# SCS_5V_RevA.net
KiCad netlist of a schematic drawn in Altium Designer
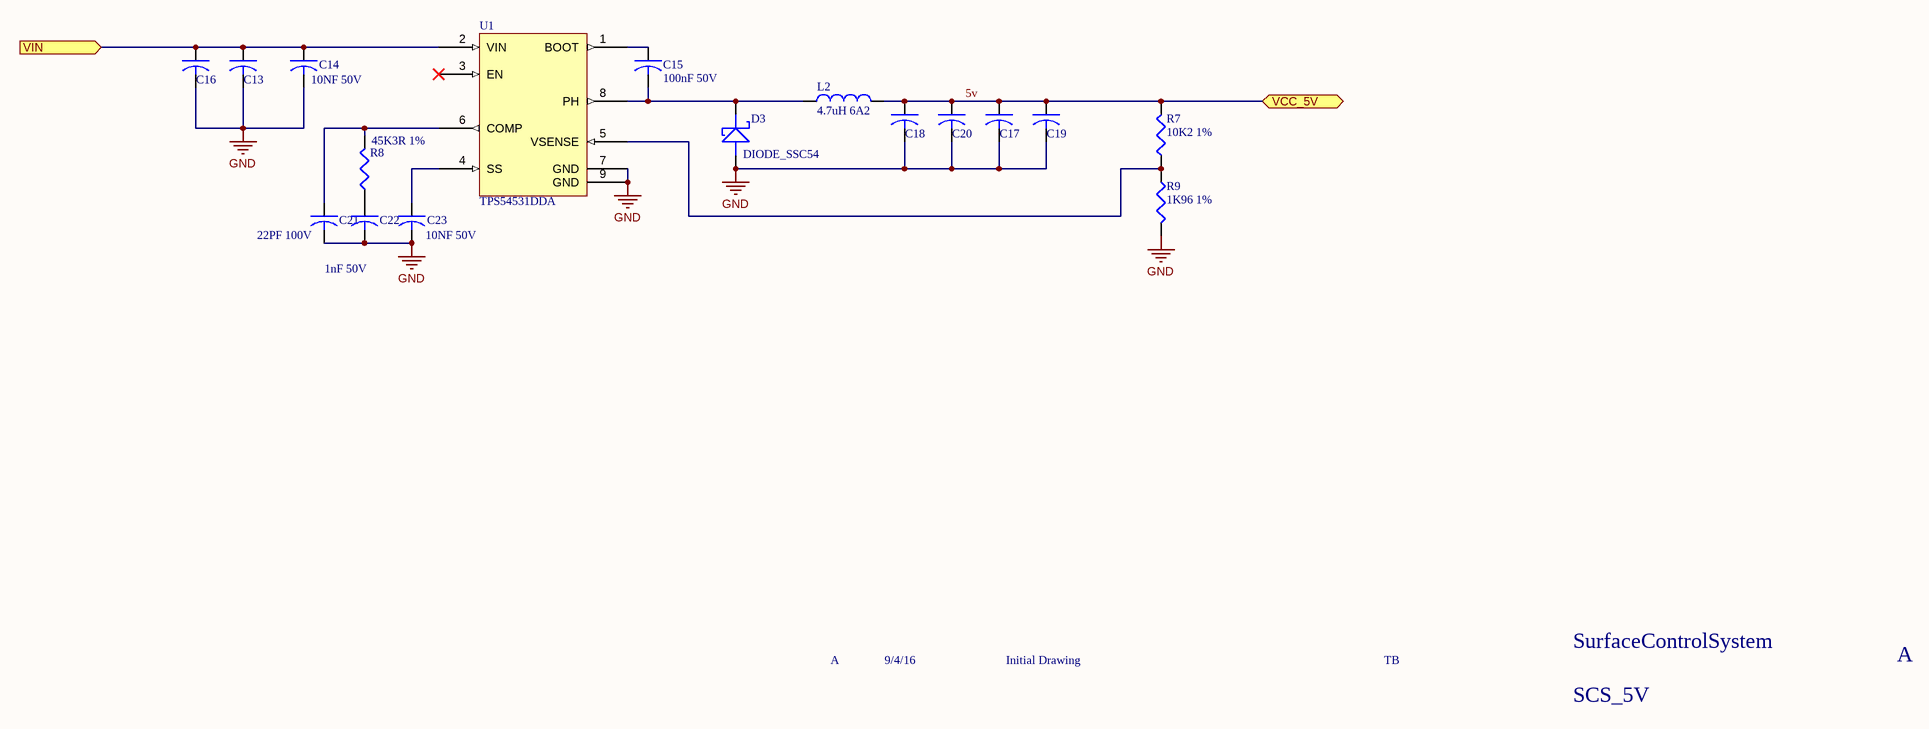
[diagram p0: SCS_5V_RevA.SchDoc]

(export (version "E")
  (design (tool "Eeschema 10.0.6"))
  (components
    (comp (ref "C13")
      (value "10UF 25V")
      (footprint "1206")
      (description "CAP CER 10UF 25V 10% X5R 1206")
      (fields (field (name "MANUFACTURER") "Murata"))
      (libsource (lib "Caps") (part "CAP_10UF_25V_10%_1206"))
    )
    (comp (ref "C14")
      (value "10NF 50V")
      (footprint "0603")
      (description "CAP CER 10NF 50V 10% X7R 0603")
      (fields (field (name "MANUFACTURER") "Murata"))
      (libsource (lib "Regulators") (part "CAP_10NF_50V_10%_0603"))
    )
    (comp (ref "C15")
      (value "100nF 50V")
      (footprint "0603")
      (description "CAP CER 100nF 50V 10% X7R 0603")
      (fields (field (name "MANUFACTURER") "Murata"))
      (libsource (lib "Caps") (part "CAP_100NF_50V_10%_0603"))
    )
    (comp (ref "C16")
      (value "10UF 25V")
      (footprint "1206")
      (description "CAP CER 10UF 25V 10% X5R 1206")
      (fields (field (name "MANUFACTURER") "Murata"))
      (libsource (lib "Caps") (part "CAP_10UF_25V_10%_1206"))
    )
    (comp (ref "C17")
      (value "10UF 25V")
      (footprint "1206")
      (description "CAP CER 10UF 25V 10% X5R 1206")
      (fields (field (name "MANUFACTURER") "Murata"))
      (libsource (lib "Caps") (part "CAP_10UF_25V_10%_1206"))
    )
    (comp (ref "C18")
      (value "10UF 25V")
      (footprint "1206")
      (description "CAP CER 10UF 25V 10% X5R 1206")
      (fields (field (name "MANUFACTURER") "Murata"))
      (libsource (lib "Caps") (part "CAP_10UF_25V_10%_1206"))
    )
    (comp (ref "C19")
      (value "10UF 25V")
      (footprint "1206")
      (description "CAP CER 10UF 25V 10% X5R 1206")
      (fields (field (name "MANUFACTURER") "Murata"))
      (libsource (lib "Caps") (part "CAP_10UF_25V_10%_1206"))
    )
    (comp (ref "C20")
      (value "10UF 25V")
      (footprint "1206")
      (description "CAP CER 10UF 25V 10% X5R 1206")
      (fields (field (name "MANUFACTURER") "Murata"))
      (libsource (lib "Caps") (part "CAP_10UF_25V_10%_1206"))
    )
    (comp (ref "C21")
      (value "22PF 100V")
      (footprint "0603")
      (description "CAP CER 22PF 100V 5% NP0 0603")
      (fields (field (name "MANUFACTURER") "Murata"))
      (libsource (lib "Caps") (part "CAP_22PF_100V_5%_0603"))
    )
    (comp (ref "C22")
      (value "1nF 50V")
      (footprint "0603")
      (description "CAP CER 1nF 50V 10% X7R 0603")
      (fields (field (name "MANUFACTURER") "Murata"))
      (libsource (lib "Caps") (part "CAP_1NF_50V_10%_0603"))
    )
    (comp (ref "C23")
      (value "10NF 50V")
      (footprint "0603")
      (description "CAP CER 10NF 50V 10% X7R 0603")
      (fields (field (name "MANUFACTURER") "Murata"))
      (libsource (lib "Regulators") (part "CAP_10NF_50V_10%_0603"))
    )
    (comp (ref "D3")
      (value "DIODE_SSC54")
      (footprint "DO-214AB")
      (description "Schottky Diode, 5A, 40V SSC54, DO214AB")
      (fields (field (name "MANUFACTURER") "Vishay"))
      (libsource (lib "Regulators") (part "DIODE_SSC54"))
    )
    (comp (ref "L2")
      (value "4.7uH 6A2")
      (footprint "Wurth744771156")
      (description "FIXED IND 4.7UH 6.2A 34 MOHM")
      (fields (field (name "MANUFACTURER") "Wurth Electronics Inc"))
      (libsource (lib "Inductors") (part "IND_4.7uH_6A2"))
    )
    (comp (ref "R7")
      (value "10K2 1%")
      (footprint "0603")
      (description "Resistor, 10K2, 1%, 0603")
      (fields (field (name "MANUFACTURER") "Yageo"))
      (libsource (lib "Resistors") (part "RES_10K2_1%_0603"))
    )
    (comp (ref "R8")
      (value "45K3R 1%")
      (footprint "0603")
      (description "Resistor, 45K3, 1%, 0603")
      (fields (field (name "MANUFACTURER") "Bourns Inc"))
      (libsource (lib "Resistors") (part "RES_45K3_1%_0603"))
    )
    (comp (ref "R9")
      (value "1K96 1%")
      (footprint "0603")
      (description "Resistor, 1K96, 1%, 0603")
      (fields (field (name "MANUFACTURER") "Yageo"))
      (libsource (lib "Resistors") (part "RES_1K96_1%_0603"))
    )
    (comp (ref "U1")
      (value "TPS54531DDA")
      (footprint "PSOP-8")
      (description "SMPS")
      (fields (field (name "MANUFACTURER") "TI"))
      (libsource (lib "IC") (part "IC_SMPS_TPS54531"))
    )
  )
  (nets
    (net (code "1") (name "/5v") (class "Default")
      (node (ref "C17") (pin "1") (pinfunction "1_1") (pintype "passive"))
      (node (ref "C18") (pin "1") (pinfunction "1_1") (pintype "passive"))
      (node (ref "C19") (pin "1") (pinfunction "1_1") (pintype "passive"))
      (node (ref "C20") (pin "1") (pinfunction "1_1") (pintype "passive"))
      (node (ref "L2") (pin "2") (pinfunction "2_2") (pintype "passive"))
      (node (ref "R7") (pin "2") (pintype "passive"))
    )
    (net (code "2") (name "/VIN") (class "Default")
      (node (ref "C13") (pin "1") (pinfunction "1_1") (pintype "passive"))
      (node (ref "C14") (pin "1") (pinfunction "1_1") (pintype "passive"))
      (node (ref "C16") (pin "1") (pinfunction "1_1") (pintype "passive"))
      (node (ref "U1") (pin "2") (pinfunction "VIN_2") (pintype "input"))
    )
    (net (code "3") (name "GND") (class "Default")
      (node (ref "C13") (pin "2") (pinfunction "2_2") (pintype "passive"))
      (node (ref "C14") (pin "2") (pinfunction "2_2") (pintype "passive"))
      (node (ref "C16") (pin "2") (pinfunction "2_2") (pintype "passive"))
      (node (ref "C17") (pin "2") (pinfunction "2_2") (pintype "passive"))
      (node (ref "C18") (pin "2") (pinfunction "2_2") (pintype "passive"))
      (node (ref "C19") (pin "2") (pinfunction "2_2") (pintype "passive"))
      (node (ref "C20") (pin "2") (pinfunction "2_2") (pintype "passive"))
      (node (ref "C21") (pin "2") (pinfunction "2_2") (pintype "passive"))
      (node (ref "C22") (pin "2") (pinfunction "2_2") (pintype "passive"))
      (node (ref "C23") (pin "2") (pinfunction "2_2") (pintype "passive"))
      (node (ref "D3") (pin "A") (pinfunction "A_A") (pintype "passive"))
      (node (ref "R9") (pin "2") (pintype "passive"))
      (node (ref "U1") (pin "7") (pinfunction "GND_7") (pintype "power_in"))
      (node (ref "U1") (pin "9") (pinfunction "GND_9") (pintype "power_in"))
    )
    (net (code "4") (name "Net-(C22-Pad1)") (class "Default")
      (node (ref "C22") (pin "1") (pinfunction "1_1") (pintype "passive"))
      (node (ref "R8") (pin "1") (pintype "passive"))
    )
    (net (code "5") (name "Net-(U1-BOOT)") (class "Default")
      (node (ref "C15") (pin "1") (pinfunction "1_1") (pintype "passive"))
      (node (ref "U1") (pin "1") (pinfunction "BOOT_1") (pintype "output"))
    )
    (net (code "6") (name "Net-(U1-COMP)") (class "Default")
      (node (ref "C21") (pin "1") (pinfunction "1_1") (pintype "passive"))
      (node (ref "R8") (pin "2") (pintype "passive"))
      (node (ref "U1") (pin "6") (pinfunction "COMP_6") (pintype "output"))
    )
    (net (code "7") (name "Net-(U1-PH)") (class "Default")
      (node (ref "C15") (pin "2") (pinfunction "2_2") (pintype "passive"))
      (node (ref "D3") (pin "K") (pinfunction "K_K") (pintype "passive"))
      (node (ref "L2") (pin "1") (pinfunction "1_1") (pintype "passive"))
      (node (ref "U1") (pin "8") (pinfunction "PH_8") (pintype "output"))
    )
    (net (code "8") (name "Net-(U1-SS)") (class "Default")
      (node (ref "C23") (pin "1") (pinfunction "1_1") (pintype "passive"))
      (node (ref "U1") (pin "4") (pinfunction "SS_4") (pintype "input"))
    )
    (net (code "9") (name "Net-(U1-VSENSE)") (class "Default")
      (node (ref "R7") (pin "1") (pintype "passive"))
      (node (ref "R9") (pin "1") (pintype "passive"))
      (node (ref "U1") (pin "5") (pinfunction "VSENSE_5") (pintype "input"))
    )
    (net (code "10") (name "unconnected-(U1-EN-Pad3)") (class "Default")
      (node (ref "U1") (pin "3") (pinfunction "EN_3") (pintype "input+no_connect"))
    )
  )
)
